# esp32-toy-motor-controller.net
KiCad netlist of a schematic drawn in EasyEDA Pro
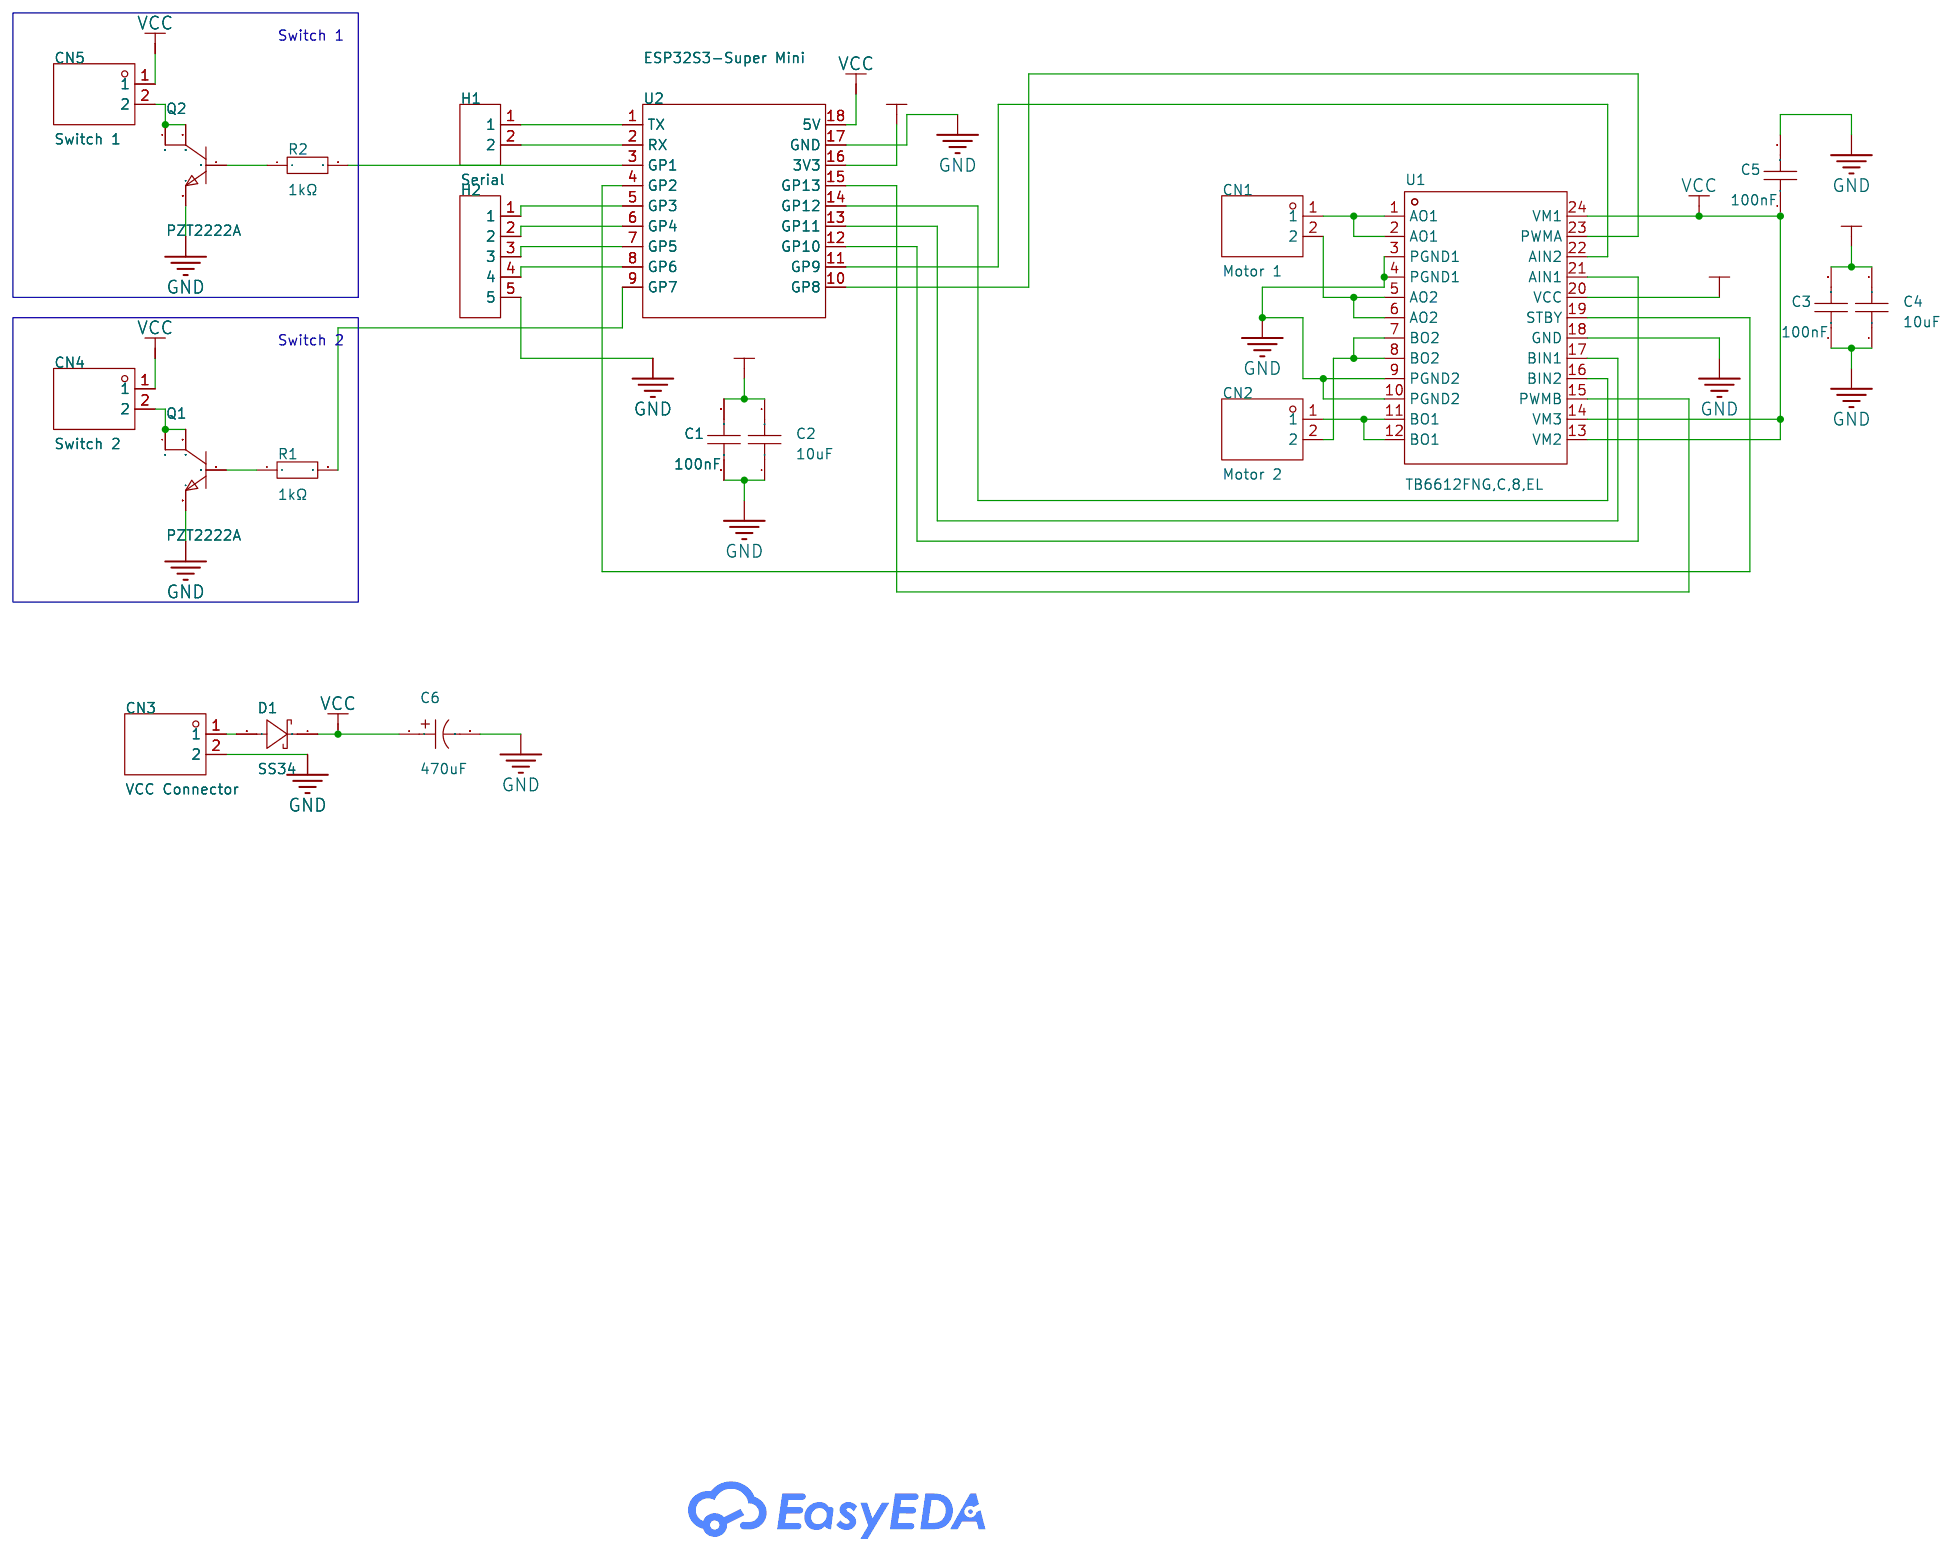
[diagram p0: schematic sheet]

(export (version "E")
  (design (tool "Eeschema 10.0.6"))
  (components
    (comp (ref "C1")
      (value "100nF")
      (footprint "easyedapro:C0805")
      (description "Capacitance:100nF Tolerance:±10% Tolerance:±10% Voltage Rating:50V Temperature Coefficient:-")
      (fields
        (field (name "Manufacturer Part") "CT41G-0805-2X1-50V-0.1uF-K(N)")
        (field (name "Manufacturer") "TORCH(火炬)")
      )
      (libsource (lib "easyedapro") (part "CT41G-0805-2X1-50V-0.1UF-K(N)"))
    )
    (comp (ref "C2")
      (value "10uF")
      (footprint "easyedapro:C0805")
      (description "Capacitance:10uF Tolerance:±10% Tolerance:±10% Voltage Rating:50V Temperature Coefficient:X5R")
      (fields
        (field (name "Manufacturer Part") "GRM21BR61H106KE43L")
        (field (name "Manufacturer") "muRata(村田)")
      )
      (libsource (lib "easyedapro") (part "GRM21BR61H106KE43L"))
    )
    (comp (ref "C3")
      (value "100nF")
      (footprint "easyedapro:C0805")
      (description "Capacitance:100nF Tolerance:±10% Tolerance:±10% Voltage Rating:50V Temperature Coefficient:-")
      (fields
        (field (name "Manufacturer Part") "CT41G-0805-2X1-50V-0.1uF-K(N)")
        (field (name "Manufacturer") "TORCH(火炬)")
      )
      (libsource (lib "easyedapro") (part "CT41G-0805-2X1-50V-0.1UF-K(N)"))
    )
    (comp (ref "C4")
      (value "10uF")
      (footprint "easyedapro:C0805")
      (description "Capacitance:10uF Tolerance:±10% Tolerance:±10% Voltage Rating:50V Temperature Coefficient:X5R")
      (fields
        (field (name "Manufacturer Part") "GRM21BR61H106KE43L")
        (field (name "Manufacturer") "muRata(村田)")
      )
      (libsource (lib "easyedapro") (part "GRM21BR61H106KE43L"))
    )
    (comp (ref "C5")
      (value "100nF")
      (footprint "easyedapro:C0805")
      (description "Capacitance:100nF Tolerance:±10% Tolerance:±10% Voltage Rating:50V Temperature Coefficient:-")
      (fields
        (field (name "Manufacturer Part") "CT41G-0805-2X1-50V-0.1uF-K(N)")
        (field (name "Manufacturer") "TORCH(火炬)")
      )
      (libsource (lib "easyedapro") (part "CT41G-0805-2X1-50V-0.1UF-K(N)"))
    )
    (comp (ref "C6")
      (value "470uF")
      (footprint "easyedapro:CAP-TH_BD8.0-P3.50-D0.5-FD")
      (fields (field (name "Manufacturer Part") "16V470uF CD110") (field (name "Manufacturer") "HRK(鸿瑞凯电子)"))
      (libsource (lib "easyedapro") (part "16V470UF CD110"))
    )
    (comp (ref "CN1")
      (value "Motor 1")
      (footprint "easyedapro:CONN-TH_B2B-XH-A-LF-SN")
      (fields (field (name "Manufacturer Part") "B2B-XH-A(LF)(SN)") (field (name "Manufacturer") "JST"))
      (libsource (lib "easyedapro") (part "B2B-XH-A (LF)(SN)"))
    )
    (comp (ref "CN2")
      (value "Motor 2")
      (footprint "easyedapro:CONN-TH_B2B-XH-A-LF-SN")
      (fields (field (name "Manufacturer Part") "B2B-XH-A(LF)(SN)") (field (name "Manufacturer") "JST"))
      (libsource (lib "easyedapro") (part "B2B-XH-A (LF)(SN)"))
    )
    (comp (ref "CN3")
      (value "VCC Connector")
      (footprint "easyedapro:CONN-TH_B2B-XH-A-LF-SN")
      (fields (field (name "Manufacturer Part") "B2B-XH-A(LF)(SN)") (field (name "Manufacturer") "JST"))
      (libsource (lib "easyedapro") (part "B2B-XH-A (LF)(SN)"))
    )
    (comp (ref "CN4")
      (value "Switch 2")
      (footprint "easyedapro:CONN-TH_B2B-XH-A-LF-SN")
      (fields (field (name "Manufacturer Part") "B2B-XH-A(LF)(SN)") (field (name "Manufacturer") "JST"))
      (libsource (lib "easyedapro") (part "B2B-XH-A (LF)(SN)"))
    )
    (comp (ref "CN5")
      (value "Switch 1")
      (footprint "easyedapro:CONN-TH_B2B-XH-A-LF-SN")
      (fields (field (name "Manufacturer Part") "B2B-XH-A(LF)(SN)") (field (name "Manufacturer") "JST"))
      (libsource (lib "easyedapro") (part "B2B-XH-A (LF)(SN)"))
    )
    (comp (ref "D1")
      (value "SS34")
      (footprint "easyedapro:SMA_L4.3-W2.5-LS5.0-RD")
      (fields (field (name "Manufacturer") "Wild Goose(威谷)"))
      (libsource (lib "easyedapro") (part "SS34_C20622488"))
    )
    (comp (ref "H1")
      (value "Serial")
      (footprint "easyedapro:HDR-TH_2P-P2.54-V-M")
      (fields
        (field (name "Manufacturer Part") "HX PH254-01-02-Z-L11.5 male header connector")
        (field (name "Manufacturer") "hanxia(韩下)")
      )
      (libsource (lib "easyedapro") (part "HX PH254-01-02-Z-L11.5 MALE HEADER CONNECTOR"))
    )
    (comp (ref "H2")
      (value "IO")
      (footprint "easyedapro:HDR-TH_5P-P2.54-V-M-3")
      (fields
        (field (name "Manufacturer Part") "PZ2.54-S05P-A60")
        (field (name "Manufacturer") "JXTCONN(聚兴泰)")
      )
      (libsource (lib "easyedapro") (part "PZ2.54-S05P-A60"))
    )
    (comp (ref "Q1")
      (value "PZT2222A")
      (footprint "easyedapro:SOT-223-3_L6.5-W3.4-P2.30-LS7.0-BR")
      (fields (field (name "Manufacturer") "CJ(江苏长电/长晶)"))
      (libsource (lib "easyedapro") (part "PZT2222A"))
    )
    (comp (ref "Q2")
      (value "PZT2222A")
      (footprint "easyedapro:SOT-223-3_L6.5-W3.4-P2.30-LS7.0-BR")
      (fields (field (name "Manufacturer") "CJ(江苏长电/长晶)"))
      (libsource (lib "easyedapro") (part "PZT2222A"))
    )
    (comp (ref "R1")
      (value "1kΩ")
      (footprint "easyedapro:R0805")
      (fields
        (field (name "Manufacturer Part") "0805W8F1001T5E")
        (field (name "Manufacturer") "UNI-ROYAL(厚声)")
      )
      (libsource (lib "easyedapro") (part "0805W8F1001T5E"))
    )
    (comp (ref "R2")
      (value "1kΩ")
      (footprint "easyedapro:R0805")
      (fields
        (field (name "Manufacturer Part") "0805W8F1001T5E")
        (field (name "Manufacturer") "UNI-ROYAL(厚声)")
      )
      (libsource (lib "easyedapro") (part "0805W8F1001T5E"))
    )
    (comp (ref "U1")
      (value "TB6612FNG,C,8,EL")
      (footprint "easyedapro:SSOP-24_L8.3-W5.6-P0.65-LS7.6-BL")
      (fields (field (name "Manufacturer") "TOSHIBA(东芝)"))
      (libsource (lib "easyedapro") (part "TB6612FNG,C,8,EL"))
    )
    (comp (ref "U2")
      (value "ESP32S3-Super Mini")
      (footprint "easyedapro:COMM-SMD_16P-L22.5-W18.0-P2.54-TL")
      (libsource (lib "easyedapro") (part "ESP32C3-SUPERMINI"))
    )
  )
  (nets
    (net (code "1") (name "+3.3V") (class "Default")
      (node (ref "C1") (pin "2") (pinfunction "2_2") (pintype "unspecified"))
      (node (ref "C2") (pin "2") (pinfunction "2_2") (pintype "unspecified"))
      (node (ref "C3") (pin "2") (pinfunction "2_2") (pintype "unspecified"))
      (node (ref "C4") (pin "2") (pinfunction "2_2") (pintype "unspecified"))
      (node (ref "U1") (pin "20") (pinfunction "VCC_20") (pintype "unspecified"))
      (node (ref "U2") (pin "16") (pinfunction "3V3_16") (pintype "unspecified"))
    )
    (net (code "2") (name "GND") (class "Default")
      (node (ref "C1") (pin "1") (pinfunction "1_1") (pintype "unspecified"))
      (node (ref "C2") (pin "1") (pinfunction "1_1") (pintype "unspecified"))
      (node (ref "C3") (pin "1") (pinfunction "1_1") (pintype "unspecified"))
      (node (ref "C4") (pin "1") (pinfunction "1_1") (pintype "unspecified"))
      (node (ref "C5") (pin "2") (pinfunction "2_2") (pintype "unspecified"))
      (node (ref "C6") (pin "2") (pinfunction "2_2") (pintype "input"))
      (node (ref "CN3") (pin "2") (pinfunction "2_2") (pintype "unspecified"))
      (node (ref "H2") (pin "5") (pinfunction "5_5") (pintype "unspecified"))
      (node (ref "Q1") (pin "3") (pinfunction "E_3") (pintype "unspecified"))
      (node (ref "Q2") (pin "3") (pinfunction "E_3") (pintype "unspecified"))
      (node (ref "U1") (pin "10") (pinfunction "PGND2_10") (pintype "unspecified"))
      (node (ref "U1") (pin "18") (pinfunction "GND_18") (pintype "unspecified"))
      (node (ref "U1") (pin "3") (pinfunction "PGND1_3") (pintype "unspecified"))
      (node (ref "U1") (pin "4") (pinfunction "PGND1_4") (pintype "unspecified"))
      (node (ref "U1") (pin "9") (pinfunction "PGND2_9") (pintype "unspecified"))
      (node (ref "U2") (pin "17") (pinfunction "GND_17") (pintype "unspecified"))
    )
    (net (code "3") (name "Net-(CN1-Pad1)") (class "Default")
      (node (ref "CN1") (pin "1") (pinfunction "1_1") (pintype "unspecified"))
      (node (ref "U1") (pin "1") (pinfunction "AO1_1") (pintype "unspecified"))
      (node (ref "U1") (pin "2") (pinfunction "AO1_2") (pintype "unspecified"))
    )
    (net (code "4") (name "Net-(CN1-Pad2)") (class "Default")
      (node (ref "CN1") (pin "2") (pinfunction "2_2") (pintype "unspecified"))
      (node (ref "U1") (pin "5") (pinfunction "AO2_5") (pintype "unspecified"))
      (node (ref "U1") (pin "6") (pinfunction "AO2_6") (pintype "unspecified"))
    )
    (net (code "5") (name "Net-(CN2-Pad1)") (class "Default")
      (node (ref "CN2") (pin "1") (pinfunction "1_1") (pintype "unspecified"))
      (node (ref "U1") (pin "11") (pinfunction "BO1_11") (pintype "unspecified"))
      (node (ref "U1") (pin "12") (pinfunction "BO1_12") (pintype "unspecified"))
    )
    (net (code "6") (name "Net-(CN2-Pad2)") (class "Default")
      (node (ref "CN2") (pin "2") (pinfunction "2_2") (pintype "unspecified"))
      (node (ref "U1") (pin "7") (pinfunction "BO2_7") (pintype "unspecified"))
      (node (ref "U1") (pin "8") (pinfunction "BO2_8") (pintype "unspecified"))
    )
    (net (code "7") (name "Net-(CN4-Pad2)") (class "Default")
      (node (ref "CN4") (pin "2") (pinfunction "2_2") (pintype "unspecified"))
      (node (ref "Q1") (pin "2") (pinfunction "C_2") (pintype "unspecified"))
      (node (ref "Q1") (pin "4") (pinfunction "C_4") (pintype "unspecified"))
    )
    (net (code "8") (name "Net-(CN5-Pad2)") (class "Default")
      (node (ref "CN5") (pin "2") (pinfunction "2_2") (pintype "unspecified"))
      (node (ref "Q2") (pin "2") (pinfunction "C_2") (pintype "unspecified"))
      (node (ref "Q2") (pin "4") (pinfunction "C_4") (pintype "unspecified"))
    )
    (net (code "9") (name "Net-(D1-A)") (class "Default")
      (node (ref "CN3") (pin "1") (pinfunction "1_1") (pintype "unspecified"))
      (node (ref "D1") (pin "2") (pinfunction "A_2") (pintype "unspecified"))
    )
    (net (code "10") (name "Net-(Q1-B)") (class "Default")
      (node (ref "Q1") (pin "1") (pinfunction "B_1") (pintype "unspecified"))
      (node (ref "R1") (pin "1") (pinfunction "1_1") (pintype "input"))
    )
    (net (code "11") (name "Net-(Q2-B)") (class "Default")
      (node (ref "Q2") (pin "1") (pinfunction "B_1") (pintype "unspecified"))
      (node (ref "R2") (pin "1") (pinfunction "1_1") (pintype "input"))
    )
    (net (code "12") (name "Net-(U1-AIN1)") (class "Default")
      (node (ref "U1") (pin "21") (pinfunction "AIN1_21") (pintype "unspecified"))
      (node (ref "U2") (pin "12") (pinfunction "GP10_12") (pintype "unspecified"))
    )
    (net (code "13") (name "Net-(U1-AIN2)") (class "Default")
      (node (ref "U1") (pin "22") (pinfunction "AIN2_22") (pintype "unspecified"))
      (node (ref "U2") (pin "11") (pinfunction "GP9_11") (pintype "unspecified"))
    )
    (net (code "14") (name "Net-(U1-BIN1)") (class "Default")
      (node (ref "U1") (pin "17") (pinfunction "BIN1_17") (pintype "unspecified"))
      (node (ref "U2") (pin "13") (pinfunction "GP11_13") (pintype "unspecified"))
    )
    (net (code "15") (name "Net-(U1-BIN2)") (class "Default")
      (node (ref "U1") (pin "16") (pinfunction "BIN2_16") (pintype "unspecified"))
      (node (ref "U2") (pin "14") (pinfunction "GP12_14") (pintype "unspecified"))
    )
    (net (code "16") (name "Net-(U1-PWMA)") (class "Default")
      (node (ref "U1") (pin "23") (pinfunction "PWMA_23") (pintype "unspecified"))
      (node (ref "U2") (pin "10") (pinfunction "GP8_10") (pintype "unspecified"))
    )
    (net (code "17") (name "Net-(U1-PWMB)") (class "Default")
      (node (ref "U1") (pin "15") (pinfunction "PWMB_15") (pintype "unspecified"))
      (node (ref "U2") (pin "15") (pinfunction "GP13_15") (pintype "unspecified"))
    )
    (net (code "18") (name "Net-(U1-STBY)") (class "Default")
      (node (ref "U1") (pin "19") (pinfunction "STBY_19") (pintype "unspecified"))
      (node (ref "U2") (pin "4") (pinfunction "GP2_4") (pintype "unspecified"))
    )
    (net (code "19") (name "Net-(U2-GP1)") (class "Default")
      (node (ref "R2") (pin "2") (pinfunction "2_2") (pintype "input"))
      (node (ref "U2") (pin "3") (pinfunction "GP1_3") (pintype "unspecified"))
    )
    (net (code "20") (name "Net-(U2-GP3)") (class "Default")
      (node (ref "H2") (pin "1") (pinfunction "1_1") (pintype "unspecified"))
      (node (ref "U2") (pin "5") (pinfunction "GP3_5") (pintype "unspecified"))
    )
    (net (code "21") (name "Net-(U2-GP4)") (class "Default")
      (node (ref "H2") (pin "2") (pinfunction "2_2") (pintype "unspecified"))
      (node (ref "U2") (pin "6") (pinfunction "GP4_6") (pintype "unspecified"))
    )
    (net (code "22") (name "Net-(U2-GP5)") (class "Default")
      (node (ref "H2") (pin "3") (pinfunction "3_3") (pintype "unspecified"))
      (node (ref "U2") (pin "7") (pinfunction "GP5_7") (pintype "unspecified"))
    )
    (net (code "23") (name "Net-(U2-GP6)") (class "Default")
      (node (ref "H2") (pin "4") (pinfunction "4_4") (pintype "unspecified"))
      (node (ref "U2") (pin "8") (pinfunction "GP6_8") (pintype "unspecified"))
    )
    (net (code "24") (name "Net-(U2-GP7)") (class "Default")
      (node (ref "R1") (pin "2") (pinfunction "2_2") (pintype "input"))
      (node (ref "U2") (pin "9") (pinfunction "GP7_9") (pintype "unspecified"))
    )
    (net (code "25") (name "Net-(U2-RX)") (class "Default")
      (node (ref "H1") (pin "2") (pinfunction "2_2") (pintype "unspecified"))
      (node (ref "U2") (pin "2") (pinfunction "RX_2") (pintype "unspecified"))
    )
    (net (code "26") (name "Net-(U2-TX)") (class "Default")
      (node (ref "H1") (pin "1") (pinfunction "1_1") (pintype "unspecified"))
      (node (ref "U2") (pin "1") (pinfunction "TX_1") (pintype "unspecified"))
    )
    (net (code "27") (name "VCC") (class "Default")
      (node (ref "C5") (pin "1") (pinfunction "1_1") (pintype "unspecified"))
      (node (ref "C6") (pin "1") (pinfunction "1_1") (pintype "input"))
      (node (ref "CN4") (pin "1") (pinfunction "1_1") (pintype "unspecified"))
      (node (ref "CN5") (pin "1") (pinfunction "1_1") (pintype "unspecified"))
      (node (ref "D1") (pin "1") (pinfunction "C_1") (pintype "unspecified"))
      (node (ref "U1") (pin "13") (pinfunction "VM2_13") (pintype "unspecified"))
      (node (ref "U1") (pin "14") (pinfunction "VM3_14") (pintype "unspecified"))
      (node (ref "U1") (pin "24") (pinfunction "VM1_24") (pintype "unspecified"))
      (node (ref "U2") (pin "18") (pinfunction "5V_18") (pintype "unspecified"))
    )
  )
)
